# PowerSupply.net
KiCad netlist of a schematic drawn in Altium Designer
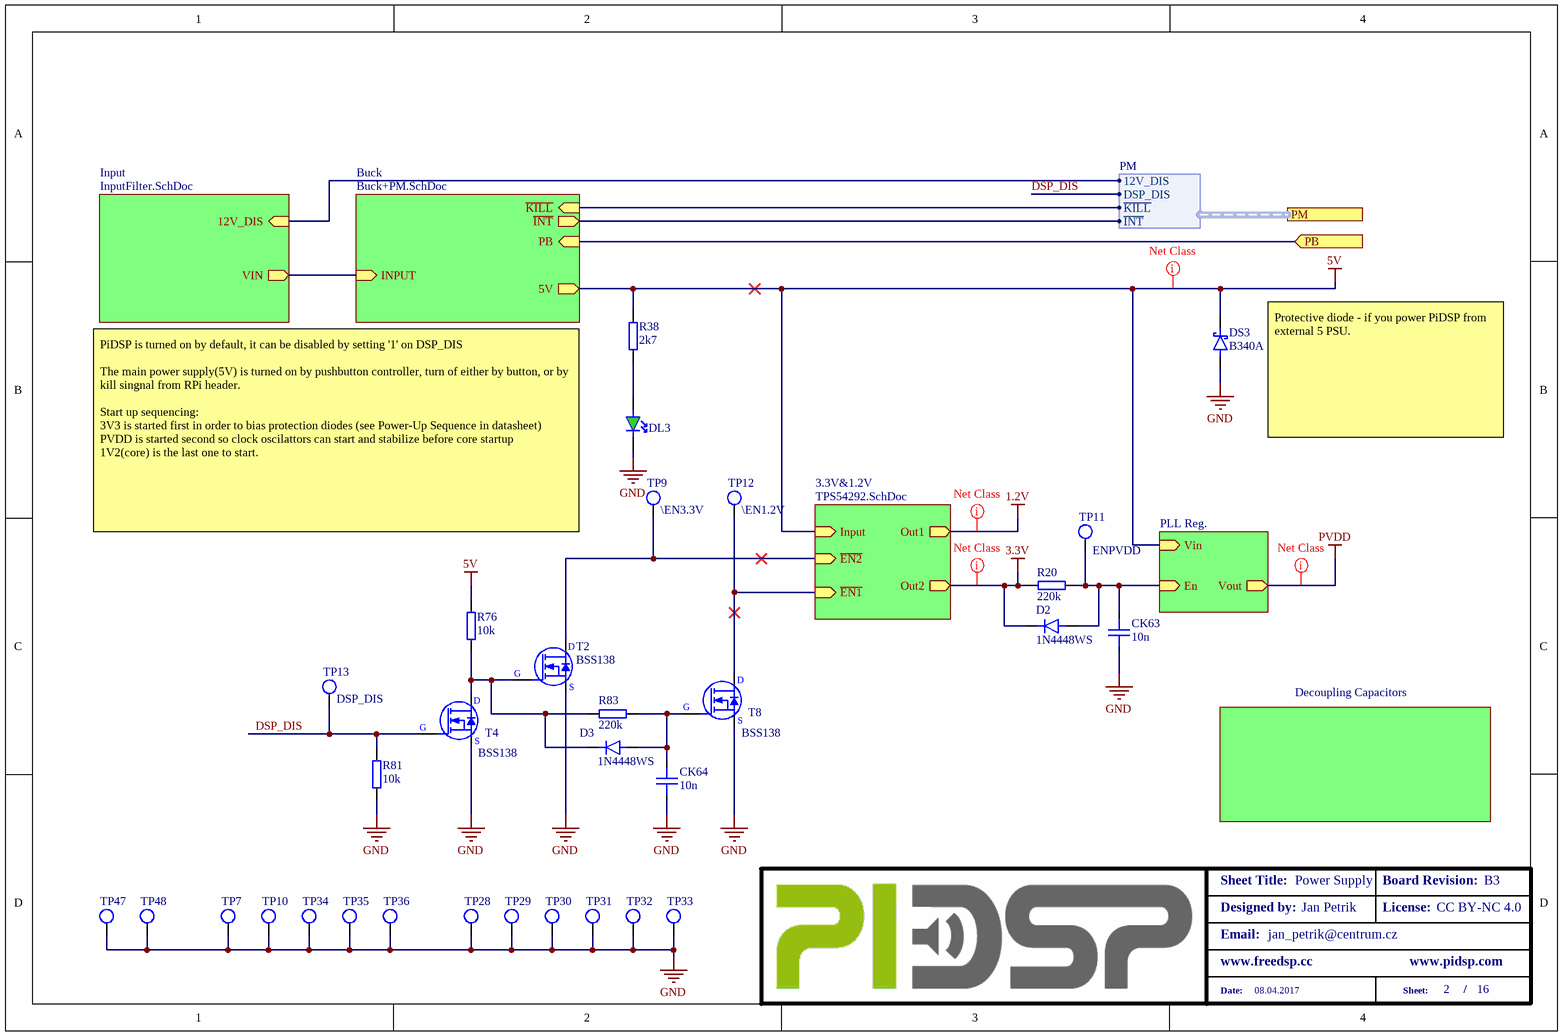
[diagram p0: PowerSupply.SchDoc]

(export (version "E")
  (design (tool "Eeschema 10.0.6"))
  (components
    (comp (ref "CK63")
      (value "10n")
      (footprint "CAPC1608X09N(SMC0603)")
      (description "MLCC")
      (fields
        (field (name "VOLTAGE") "50V")
        (field (name "TOLERANCE") "10%")
        (field (name "AUTHOR") "JP/27.03.2014")
      )
      (libsource (lib "JP_C") (part "10n-50V-0603-X7R"))
    )
    (comp (ref "CK64")
      (value "10n")
      (footprint "CAPC1608X09N(SMC0603)")
      (description "MLCC")
      (fields
        (field (name "VOLTAGE") "50V")
        (field (name "TOLERANCE") "10%")
        (field (name "AUTHOR") "JP/27.03.2014")
      )
      (libsource (lib "JP_C") (part "10n-50V-0603-X7R"))
    )
    (comp (ref "D2")
      (value "1N4448WS")
      (footprint "SOD-323")
      (description "Small signal diode")
      (fields (field (name "VOLTAGE") "75V"))
      (libsource (lib "JP_IC") (part "1N4448WS"))
    )
    (comp (ref "D3")
      (value "1N4448WS")
      (footprint "SOD-323")
      (description "Small signal diode")
      (fields (field (name "VOLTAGE") "75V"))
      (libsource (lib "JP_IC") (part "1N4448WS"))
    )
    (comp (ref "DL3")
      (value "GREEN")
      (footprint "0603diode")
      (description "Green LED, 0603")
      (fields (field (name "AUTHOR") "JP/31.3.2014"))
      (libsource (lib "IC") (part "LED_GREEN_0603"))
    )
    (comp (ref "DS3")
      (value "B340A")
      (footprint "DIOM5127X23N(SMA)")
      (description "High Current Density SMT Schottky Rectifier, 3A/40V, SMA")
      (libsource (lib "JP_IC") (part "B340A"))
    )
    (comp (ref "R20")
      (value "220k")
      (footprint "RESC1608X06N(SMR0603)")
      (description "Chip Resistor")
      (fields (field (name "AUTHOR") "JP/10.06.2014"))
      (libsource (lib "JP_R") (part "220k-100mW-0603-ThickFilm"))
    )
    (comp (ref "R38")
      (value "2k7")
      (footprint "RESC1608X06N(SMR0603)")
      (description "Chip Resistor")
      (fields (field (name "AUTHOR") "JP/26.03.2017"))
      (libsource (lib "JP_R") (part "2K7-100mW-0603-ThickFilm"))
    )
    (comp (ref "R76")
      (value "10k")
      (footprint "RESC1608X06N(SMR0603)")
      (description "Chip Resistor")
      (fields (field (name "AUTHOR") "JP/10.06.2014"))
      (libsource (lib "JP_R") (part "10k-100mW-0603-ThickFilm"))
    )
    (comp (ref "R81")
      (value "10k")
      (footprint "RESC1608X06N(SMR0603)")
      (description "Chip Resistor")
      (fields (field (name "AUTHOR") "JP/10.06.2014"))
      (libsource (lib "JP_R") (part "10k-100mW-0603-ThickFilm"))
    )
    (comp (ref "R83")
      (value "220k")
      (footprint "RESC1608X06N(SMR0603)")
      (description "Chip Resistor")
      (fields (field (name "AUTHOR") "JP/10.06.2014"))
      (libsource (lib "JP_R") (part "220k-100mW-0603-ThickFilm"))
    )
    (comp (ref "T2")
      (value "BSS138")
      (footprint "SOT95P230X110-3N(SOT23)")
      (description "N-MOSFET, Logic Level, 50V/0,22A/3.5Ohm")
      (fields (field (name "AUTHOR") "JM 2.7.2014"))
      (libsource (lib "JP_IC") (part "ET+BSS138XX0"))
    )
    (comp (ref "T4")
      (value "BSS138")
      (footprint "SOT95P230X110-3N(SOT23)")
      (description "N-MOSFET, Logic Level, 50V/0,22A/3.5Ohm")
      (fields (field (name "AUTHOR") "JM 2.7.2014"))
      (libsource (lib "JP_IC") (part "ET+BSS138XX0"))
    )
    (comp (ref "T8")
      (value "BSS138")
      (footprint "SOT95P230X110-3N(SOT23)")
      (description "N-MOSFET, Logic Level, 50V/0,22A/3.5Ohm")
      (fields (field (name "AUTHOR") "JM 2.7.2014"))
      (libsource (lib "JP_IC") (part "ET+BSS138XX0"))
    )
    (comp (ref "TP7")
      (value "GND")
      (footprint "TP_0.8/0.4_ROUND")
      (description "Testpoint - VIA")
      (libsource (lib "JP_CONN") (part "TEST_POINT_VIA"))
    )
    (comp (ref "TP9")
      (value "EN3.3V")
      (footprint "TP_0.8/0.4_ROUND")
      (description "Testpoint - VIA")
      (libsource (lib "JP_CONN") (part "TEST_POINT_VIA"))
    )
    (comp (ref "TP10")
      (value "GND")
      (footprint "TP_0.8/0.4_ROUND")
      (description "Testpoint - VIA")
      (libsource (lib "JP_CONN") (part "TEST_POINT_VIA"))
    )
    (comp (ref "TP11")
      (value "ENPVDD")
      (footprint "TP_0.8/0.4_ROUND")
      (description "Testpoint - VIA")
      (libsource (lib "JP_CONN") (part "TEST_POINT_VIA"))
    )
    (comp (ref "TP12")
      (value "EN1.2V")
      (footprint "TP_0.8/0.4_ROUND")
      (description "Testpoint - VIA")
      (libsource (lib "JP_CONN") (part "TEST_POINT_VIA"))
    )
    (comp (ref "TP13")
      (value "DSP_DIS")
      (footprint "TP_0.8/0.4_ROUND")
      (description "Testpoint - VIA")
      (libsource (lib "JP_CONN") (part "TEST_POINT_VIA"))
    )
    (comp (ref "TP28")
      (value "GND")
      (footprint "TP_0.8/0.4_ROUND")
      (description "Testpoint - VIA")
      (libsource (lib "JP_CONN") (part "TEST_POINT_VIA"))
    )
    (comp (ref "TP29")
      (value "GND")
      (footprint "TP_0.8/0.4_ROUND")
      (description "Testpoint - VIA")
      (libsource (lib "JP_CONN") (part "TEST_POINT_VIA"))
    )
    (comp (ref "TP30")
      (value "GND")
      (footprint "TP_0.8/0.4_ROUND")
      (description "Testpoint - VIA")
      (libsource (lib "JP_CONN") (part "TEST_POINT_VIA"))
    )
    (comp (ref "TP31")
      (value "GND")
      (footprint "TP_0.8/0.4_ROUND")
      (description "Testpoint - VIA")
      (libsource (lib "JP_CONN") (part "TEST_POINT_VIA"))
    )
    (comp (ref "TP32")
      (value "GND")
      (footprint "TP_0.8/0.4_ROUND")
      (description "Testpoint - VIA")
      (libsource (lib "JP_CONN") (part "TEST_POINT_VIA"))
    )
    (comp (ref "TP33")
      (value "GND")
      (footprint "TP_0.8/0.4_ROUND")
      (description "Testpoint - VIA")
      (libsource (lib "JP_CONN") (part "TEST_POINT_VIA"))
    )
    (comp (ref "TP34")
      (value "GND")
      (footprint "TP_0.8/0.4_ROUND")
      (description "Testpoint - VIA")
      (libsource (lib "JP_CONN") (part "TEST_POINT_VIA"))
    )
    (comp (ref "TP35")
      (value "GND")
      (footprint "TP_0.8/0.4_ROUND")
      (description "Testpoint - VIA")
      (libsource (lib "JP_CONN") (part "TEST_POINT_VIA"))
    )
    (comp (ref "TP36")
      (value "GND")
      (footprint "TP_0.8/0.4_ROUND")
      (description "Testpoint - VIA")
      (libsource (lib "JP_CONN") (part "TEST_POINT_VIA"))
    )
    (comp (ref "TP47")
      (value "GND")
      (footprint "TP_0.8/0.4_ROUND")
      (description "Testpoint - VIA")
      (libsource (lib "JP_CONN") (part "TEST_POINT_VIA"))
    )
    (comp (ref "TP48")
      (value "GND")
      (footprint "TP_0.8/0.4_ROUND")
      (description "Testpoint - VIA")
      (libsource (lib "JP_CONN") (part "TEST_POINT_VIA"))
    )
  )
  (nets
    (net (code "3") (name "/DSP_DIS") (class "Default")
      (node (ref "R81") (pin "2") (pinfunction "2_2") (pintype "passive"))
      (node (ref "T4") (pin "1") (pinfunction "G_1") (pintype "passive"))
      (node (ref "TP13") (pin "1") (pintype "passive"))
    )
    (net (code "4") (name "/En") (class "Default")
      (node (ref "CK63") (pin "1") (pinfunction "1_1") (pintype "passive"))
      (node (ref "D2") (pin "2") (pinfunction "A_2") (pintype "passive"))
      (node (ref "R20") (pin "1") (pinfunction "1_1") (pintype "passive"))
      (node (ref "TP11") (pin "1") (pintype "passive"))
    )
    (net (code "8") (name "/~{EN1}") (class "Default")
      (node (ref "T8") (pin "3") (pinfunction "D_3") (pintype "passive"))
      (node (ref "TP12") (pin "1") (pintype "passive"))
    )
    (net (code "9") (name "/~{EN2}") (class "Default")
      (node (ref "T2") (pin "3") (pinfunction "D_3") (pintype "passive"))
      (node (ref "TP9") (pin "1") (pintype "passive"))
    )
    (net (code "13") (name "3.3V") (class "Default")
      (node (ref "D2") (pin "1") (pinfunction "C_1") (pintype "passive"))
      (node (ref "R20") (pin "2") (pinfunction "2_2") (pintype "passive"))
    )
    (net (code "14") (name "5V") (class "Default")
      (node (ref "DS3") (pin "1") (pinfunction "C_1") (pintype "passive"))
      (node (ref "R38") (pin "1") (pinfunction "1_1") (pintype "passive"))
      (node (ref "R76") (pin "2") (pinfunction "2_2") (pintype "passive"))
    )
    (net (code "15") (name "GND") (class "Default")
      (node (ref "CK63") (pin "2") (pinfunction "2_2") (pintype "passive"))
      (node (ref "CK64") (pin "1") (pinfunction "1_1") (pintype "passive"))
      (node (ref "DL3") (pin "1") (pinfunction "C_1") (pintype "passive"))
      (node (ref "DS3") (pin "2") (pinfunction "A_2") (pintype "passive"))
      (node (ref "R81") (pin "1") (pinfunction "1_1") (pintype "passive"))
      (node (ref "T2") (pin "2") (pinfunction "S_2") (pintype "passive"))
      (node (ref "T4") (pin "2") (pinfunction "S_2") (pintype "passive"))
      (node (ref "T8") (pin "2") (pinfunction "S_2") (pintype "passive"))
      (node (ref "TP10") (pin "1") (pintype "passive"))
      (node (ref "TP28") (pin "1") (pintype "passive"))
      (node (ref "TP29") (pin "1") (pintype "passive"))
      (node (ref "TP30") (pin "1") (pintype "passive"))
      (node (ref "TP31") (pin "1") (pintype "passive"))
      (node (ref "TP32") (pin "1") (pintype "passive"))
      (node (ref "TP33") (pin "1") (pintype "passive"))
      (node (ref "TP34") (pin "1") (pintype "passive"))
      (node (ref "TP35") (pin "1") (pintype "passive"))
      (node (ref "TP36") (pin "1") (pintype "passive"))
      (node (ref "TP47") (pin "1") (pintype "passive"))
      (node (ref "TP48") (pin "1") (pintype "passive"))
      (node (ref "TP7") (pin "1") (pintype "passive"))
    )
    (net (code "16") (name "Net-(D3-A)") (class "Default")
      (node (ref "CK64") (pin "2") (pinfunction "2_2") (pintype "passive"))
      (node (ref "D3") (pin "2") (pinfunction "A_2") (pintype "passive"))
      (node (ref "R83") (pin "2") (pinfunction "2_2") (pintype "passive"))
      (node (ref "T8") (pin "1") (pinfunction "G_1") (pintype "passive"))
    )
    (net (code "17") (name "Net-(D3-C)") (class "Default")
      (node (ref "D3") (pin "1") (pinfunction "C_1") (pintype "passive"))
      (node (ref "R76") (pin "1") (pinfunction "1_1") (pintype "passive"))
      (node (ref "R83") (pin "1") (pinfunction "1_1") (pintype "passive"))
      (node (ref "T2") (pin "1") (pinfunction "G_1") (pintype "passive"))
      (node (ref "T4") (pin "3") (pinfunction "D_3") (pintype "passive"))
    )
    (net (code "18") (name "Net-(DL3-A)") (class "Default")
      (node (ref "DL3") (pin "2") (pinfunction "A_2") (pintype "passive"))
      (node (ref "R38") (pin "2") (pinfunction "2_2") (pintype "passive"))
    )
  )
)
